# PA3.net
KiCad netlist of a schematic drawn in EAGLE
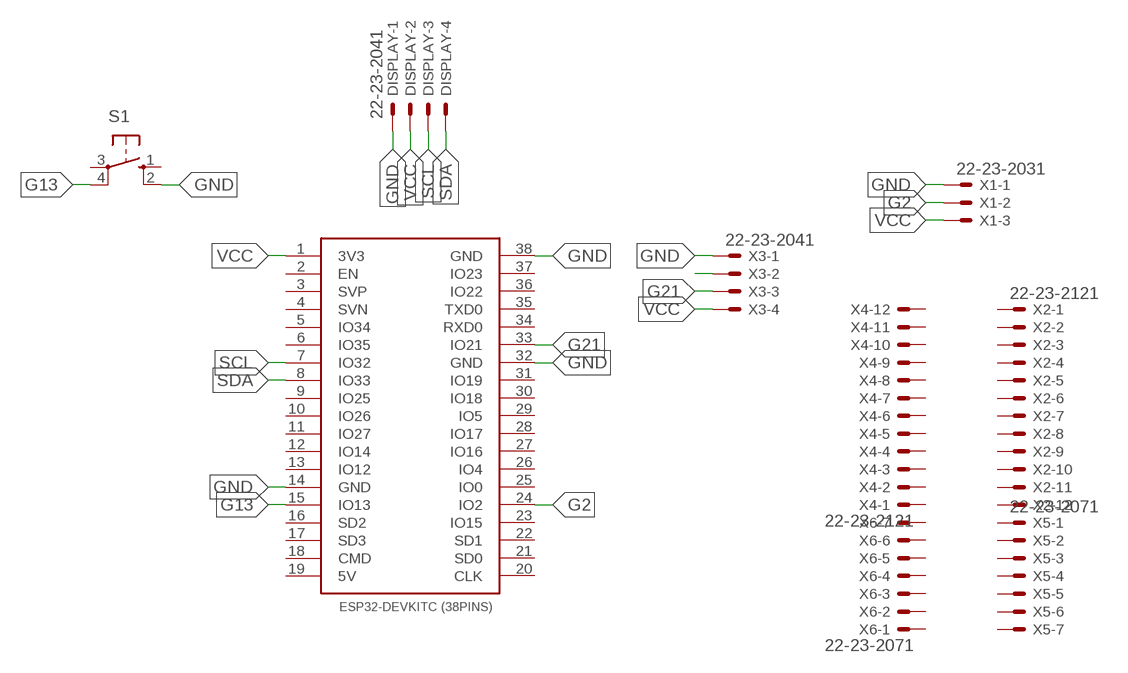
[diagram p0: schematic, sheet 1]

(export (version "E")
  (design (tool "Eeschema 10.0.6"))
  (components
    (comp (ref "DISPLAY")
      (value "22-23-2041")
      (footprint "eagle-import:22-23-2041")
      (fields (field (name "MF") "MOLEX"))
      (libsource (lib "eagle-import") (part "22-23-2041"))
    )
    (comp (ref "ESP32-DEVKITC(38PINS)1")
      (value "ESP32DEVKITC_38PINS")
      (footprint "eagle-import:ESP32-DEVKITC")
      (libsource (lib "eagle-import") (part "ESP32DEVKITC_38PINS"))
    )
    (comp (ref "S1")
      (value "10-XX")
      (footprint "eagle-import:B3F-10XX")
      (fields (field (name "MPN") "B3F-1000"))
      (libsource (lib "eagle-import") (part "10-XX"))
    )
    (comp (ref "X1")
      (value "22-23-2031")
      (footprint "eagle-import:22-23-2031")
      (fields (field (name "MF") "MOLEX"))
      (libsource (lib "eagle-import") (part "22-23-2031"))
    )
    (comp (ref "X2")
      (value "22-23-2121")
      (footprint "eagle-import:22-23-2121")
      (fields (field (name "MF") "MOLEX"))
      (libsource (lib "eagle-import") (part "22-23-2121"))
    )
    (comp (ref "X3")
      (value "22-23-2041")
      (footprint "eagle-import:22-23-2041")
      (fields (field (name "MF") "MOLEX"))
      (libsource (lib "eagle-import") (part "22-23-2041"))
    )
    (comp (ref "X4")
      (value "22-23-2121")
      (footprint "eagle-import:22-23-2121")
      (fields (field (name "MF") "MOLEX"))
      (libsource (lib "eagle-import") (part "22-23-2121"))
    )
    (comp (ref "X5")
      (value "22-23-2071")
      (footprint "eagle-import:22-23-2071")
      (fields (field (name "MF") "MOLEX"))
      (libsource (lib "eagle-import") (part "22-23-2071"))
    )
    (comp (ref "X6")
      (value "22-23-2071")
      (footprint "eagle-import:22-23-2071")
      (fields (field (name "MF") "MOLEX"))
      (libsource (lib "eagle-import") (part "22-23-2071"))
    )
  )
  (nets
    (net (code "1") (name "G2") (class "Default")
      (node (ref "ESP32-DEVKITC(38PINS)1") (pin "24") (pinfunction "IO2_24") (pintype "bidirectional"))
      (node (ref "X1") (pin "2") (pinfunction "S_2") (pintype "passive"))
    )
    (net (code "2") (name "G13") (class "Default")
      (node (ref "ESP32-DEVKITC(38PINS)1") (pin "15") (pinfunction "IO13_15") (pintype "bidirectional"))
      (node (ref "S1") (pin "4") (pinfunction "P1_4") (pintype "passive"))
    )
    (net (code "3") (name "G21") (class "Default")
      (node (ref "ESP32-DEVKITC(38PINS)1") (pin "33") (pinfunction "IO21_33") (pintype "bidirectional"))
      (node (ref "X3") (pin "3") (pinfunction "S_3") (pintype "passive"))
    )
    (net (code "4") (name "GND") (class "Default")
      (node (ref "DISPLAY") (pin "1") (pinfunction "S_1") (pintype "passive"))
      (node (ref "ESP32-DEVKITC(38PINS)1") (pin "14") (pinfunction "GND_14") (pintype "bidirectional"))
      (node (ref "ESP32-DEVKITC(38PINS)1") (pin "32") (pinfunction "GND_32") (pintype "bidirectional"))
      (node (ref "ESP32-DEVKITC(38PINS)1") (pin "38") (pinfunction "GND_38") (pintype "bidirectional"))
      (node (ref "S1") (pin "2") (pinfunction "S1_2") (pintype "passive"))
      (node (ref "X1") (pin "1") (pinfunction "S_1") (pintype "passive"))
      (node (ref "X3") (pin "1") (pinfunction "S_1") (pintype "passive"))
    )
    (net (code "5") (name "SCL") (class "Default")
      (node (ref "DISPLAY") (pin "3") (pinfunction "S_3") (pintype "passive"))
      (node (ref "ESP32-DEVKITC(38PINS)1") (pin "7") (pinfunction "IO32_7") (pintype "bidirectional"))
    )
    (net (code "6") (name "SDA") (class "Default")
      (node (ref "DISPLAY") (pin "4") (pinfunction "S_4") (pintype "passive"))
      (node (ref "ESP32-DEVKITC(38PINS)1") (pin "8") (pinfunction "IO33_8") (pintype "bidirectional"))
    )
    (net (code "7") (name "VCC") (class "Default")
      (node (ref "DISPLAY") (pin "2") (pinfunction "S_2") (pintype "passive"))
      (node (ref "ESP32-DEVKITC(38PINS)1") (pin "1") (pinfunction "3V3_1") (pintype "bidirectional"))
      (node (ref "X1") (pin "3") (pinfunction "S_3") (pintype "passive"))
      (node (ref "X3") (pin "4") (pinfunction "S_4") (pintype "passive"))
    )
    (net (code "8") (name "unconnected-(ESP32-DEVKITC(38PINS)1-5V-Pad19)") (class "Default")
      (node (ref "ESP32-DEVKITC(38PINS)1") (pin "19") (pinfunction "5V_19") (pintype "bidirectional"))
    )
    (net (code "9") (name "unconnected-(ESP32-DEVKITC(38PINS)1-CLK-Pad20)") (class "Default")
      (node (ref "ESP32-DEVKITC(38PINS)1") (pin "20") (pinfunction "CLK_20") (pintype "bidirectional"))
    )
    (net (code "10") (name "unconnected-(ESP32-DEVKITC(38PINS)1-CMD-Pad18)") (class "Default")
      (node (ref "ESP32-DEVKITC(38PINS)1") (pin "18") (pinfunction "CMD_18") (pintype "bidirectional"))
    )
    (net (code "11") (name "unconnected-(ESP32-DEVKITC(38PINS)1-EN-Pad2)") (class "Default")
      (node (ref "ESP32-DEVKITC(38PINS)1") (pin "2") (pinfunction "EN_2") (pintype "bidirectional"))
    )
    (net (code "12") (name "unconnected-(ESP32-DEVKITC(38PINS)1-IO0-Pad25)") (class "Default")
      (node (ref "ESP32-DEVKITC(38PINS)1") (pin "25") (pinfunction "IO0_25") (pintype "bidirectional"))
    )
    (net (code "13") (name "unconnected-(ESP32-DEVKITC(38PINS)1-IO4-Pad26)") (class "Default")
      (node (ref "ESP32-DEVKITC(38PINS)1") (pin "26") (pinfunction "IO4_26") (pintype "bidirectional"))
    )
    (net (code "14") (name "unconnected-(ESP32-DEVKITC(38PINS)1-IO5-Pad29)") (class "Default")
      (node (ref "ESP32-DEVKITC(38PINS)1") (pin "29") (pinfunction "IO5_29") (pintype "bidirectional"))
    )
    (net (code "15") (name "unconnected-(ESP32-DEVKITC(38PINS)1-IO12-Pad13)") (class "Default")
      (node (ref "ESP32-DEVKITC(38PINS)1") (pin "13") (pinfunction "IO12_13") (pintype "bidirectional"))
    )
    (net (code "16") (name "unconnected-(ESP32-DEVKITC(38PINS)1-IO14-Pad12)") (class "Default")
      (node (ref "ESP32-DEVKITC(38PINS)1") (pin "12") (pinfunction "IO14_12") (pintype "bidirectional"))
    )
    (net (code "17") (name "unconnected-(ESP32-DEVKITC(38PINS)1-IO15-Pad23)") (class "Default")
      (node (ref "ESP32-DEVKITC(38PINS)1") (pin "23") (pinfunction "IO15_23") (pintype "bidirectional"))
    )
    (net (code "18") (name "unconnected-(ESP32-DEVKITC(38PINS)1-IO16-Pad27)") (class "Default")
      (node (ref "ESP32-DEVKITC(38PINS)1") (pin "27") (pinfunction "IO16_27") (pintype "bidirectional"))
    )
    (net (code "19") (name "unconnected-(ESP32-DEVKITC(38PINS)1-IO17-Pad28)") (class "Default")
      (node (ref "ESP32-DEVKITC(38PINS)1") (pin "28") (pinfunction "IO17_28") (pintype "bidirectional"))
    )
    (net (code "20") (name "unconnected-(ESP32-DEVKITC(38PINS)1-IO18-Pad30)") (class "Default")
      (node (ref "ESP32-DEVKITC(38PINS)1") (pin "30") (pinfunction "IO18_30") (pintype "bidirectional"))
    )
    (net (code "21") (name "unconnected-(ESP32-DEVKITC(38PINS)1-IO19-Pad31)") (class "Default")
      (node (ref "ESP32-DEVKITC(38PINS)1") (pin "31") (pinfunction "IO19_31") (pintype "bidirectional"))
    )
    (net (code "22") (name "unconnected-(ESP32-DEVKITC(38PINS)1-IO22-Pad36)") (class "Default")
      (node (ref "ESP32-DEVKITC(38PINS)1") (pin "36") (pinfunction "IO22_36") (pintype "bidirectional"))
    )
    (net (code "23") (name "unconnected-(ESP32-DEVKITC(38PINS)1-IO23-Pad37)") (class "Default")
      (node (ref "ESP32-DEVKITC(38PINS)1") (pin "37") (pinfunction "IO23_37") (pintype "bidirectional"))
    )
    (net (code "24") (name "unconnected-(ESP32-DEVKITC(38PINS)1-IO25-Pad9)") (class "Default")
      (node (ref "ESP32-DEVKITC(38PINS)1") (pin "9") (pinfunction "IO25_9") (pintype "bidirectional"))
    )
    (net (code "25") (name "unconnected-(ESP32-DEVKITC(38PINS)1-IO26-Pad10)") (class "Default")
      (node (ref "ESP32-DEVKITC(38PINS)1") (pin "10") (pinfunction "IO26_10") (pintype "bidirectional"))
    )
    (net (code "26") (name "unconnected-(ESP32-DEVKITC(38PINS)1-IO27-Pad11)") (class "Default")
      (node (ref "ESP32-DEVKITC(38PINS)1") (pin "11") (pinfunction "IO27_11") (pintype "bidirectional"))
    )
    (net (code "27") (name "unconnected-(ESP32-DEVKITC(38PINS)1-IO34-Pad5)") (class "Default")
      (node (ref "ESP32-DEVKITC(38PINS)1") (pin "5") (pinfunction "IO34_5") (pintype "bidirectional"))
    )
    (net (code "28") (name "unconnected-(ESP32-DEVKITC(38PINS)1-IO35-Pad6)") (class "Default")
      (node (ref "ESP32-DEVKITC(38PINS)1") (pin "6") (pinfunction "IO35_6") (pintype "bidirectional"))
    )
    (net (code "29") (name "unconnected-(ESP32-DEVKITC(38PINS)1-RXD0-Pad34)") (class "Default")
      (node (ref "ESP32-DEVKITC(38PINS)1") (pin "34") (pinfunction "RXD0_34") (pintype "bidirectional"))
    )
    (net (code "30") (name "unconnected-(ESP32-DEVKITC(38PINS)1-SD0-Pad21)") (class "Default")
      (node (ref "ESP32-DEVKITC(38PINS)1") (pin "21") (pinfunction "SD0_21") (pintype "bidirectional"))
    )
    (net (code "31") (name "unconnected-(ESP32-DEVKITC(38PINS)1-SD1-Pad22)") (class "Default")
      (node (ref "ESP32-DEVKITC(38PINS)1") (pin "22") (pinfunction "SD1_22") (pintype "bidirectional"))
    )
    (net (code "32") (name "unconnected-(ESP32-DEVKITC(38PINS)1-SD2-Pad16)") (class "Default")
      (node (ref "ESP32-DEVKITC(38PINS)1") (pin "16") (pinfunction "SD2_16") (pintype "bidirectional"))
    )
    (net (code "33") (name "unconnected-(ESP32-DEVKITC(38PINS)1-SD3-Pad17)") (class "Default")
      (node (ref "ESP32-DEVKITC(38PINS)1") (pin "17") (pinfunction "SD3_17") (pintype "bidirectional"))
    )
    (net (code "34") (name "unconnected-(ESP32-DEVKITC(38PINS)1-SVN-Pad4)") (class "Default")
      (node (ref "ESP32-DEVKITC(38PINS)1") (pin "4") (pinfunction "SVN_4") (pintype "bidirectional"))
    )
    (net (code "35") (name "unconnected-(ESP32-DEVKITC(38PINS)1-SVP-Pad3)") (class "Default")
      (node (ref "ESP32-DEVKITC(38PINS)1") (pin "3") (pinfunction "SVP_3") (pintype "bidirectional"))
    )
    (net (code "36") (name "unconnected-(ESP32-DEVKITC(38PINS)1-TXD0-Pad35)") (class "Default")
      (node (ref "ESP32-DEVKITC(38PINS)1") (pin "35") (pinfunction "TXD0_35") (pintype "bidirectional"))
    )
    (net (code "37") (name "unconnected-(S1-P-Pad3)") (class "Default")
      (node (ref "S1") (pin "3") (pinfunction "P_3") (pintype "passive"))
    )
    (net (code "38") (name "unconnected-(S1-S-Pad1)") (class "Default")
      (node (ref "S1") (pin "1") (pinfunction "S_1") (pintype "passive"))
    )
    (net (code "39") (name "unconnected-(X2A-S-Pad1)") (class "Default")
      (node (ref "X2") (pin "1") (pinfunction "S_1") (pintype "passive"))
    )
    (net (code "40") (name "unconnected-(X2B-S-Pad10)") (class "Default")
      (node (ref "X2") (pin "10") (pinfunction "S_10") (pintype "passive"))
    )
    (net (code "41") (name "unconnected-(X2C-S-Pad11)") (class "Default")
      (node (ref "X2") (pin "11") (pinfunction "S_11") (pintype "passive"))
    )
    (net (code "42") (name "unconnected-(X2D-S-Pad12)") (class "Default")
      (node (ref "X2") (pin "12") (pinfunction "S_12") (pintype "passive"))
    )
    (net (code "43") (name "unconnected-(X2E-S-Pad2)") (class "Default")
      (node (ref "X2") (pin "2") (pinfunction "S_2") (pintype "passive"))
    )
    (net (code "44") (name "unconnected-(X2F-S-Pad3)") (class "Default")
      (node (ref "X2") (pin "3") (pinfunction "S_3") (pintype "passive"))
    )
    (net (code "45") (name "unconnected-(X2G-S-Pad4)") (class "Default")
      (node (ref "X2") (pin "4") (pinfunction "S_4") (pintype "passive"))
    )
    (net (code "46") (name "unconnected-(X2H-S-Pad5)") (class "Default")
      (node (ref "X2") (pin "5") (pinfunction "S_5") (pintype "passive"))
    )
    (net (code "47") (name "unconnected-(X2I-S-Pad6)") (class "Default")
      (node (ref "X2") (pin "6") (pinfunction "S_6") (pintype "passive"))
    )
    (net (code "48") (name "unconnected-(X2J-S-Pad7)") (class "Default")
      (node (ref "X2") (pin "7") (pinfunction "S_7") (pintype "passive"))
    )
    (net (code "49") (name "unconnected-(X2K-S-Pad8)") (class "Default")
      (node (ref "X2") (pin "8") (pinfunction "S_8") (pintype "passive"))
    )
    (net (code "50") (name "unconnected-(X2L-S-Pad9)") (class "Default")
      (node (ref "X2") (pin "9") (pinfunction "S_9") (pintype "passive"))
    )
    (net (code "51") (name "unconnected-(X3B-S-Pad2)") (class "Default")
      (node (ref "X3") (pin "2") (pinfunction "S_2") (pintype "passive"))
    )
    (net (code "52") (name "unconnected-(X4A-S-Pad1)") (class "Default")
      (node (ref "X4") (pin "1") (pinfunction "S_1") (pintype "passive"))
    )
    (net (code "53") (name "unconnected-(X4B-S-Pad10)") (class "Default")
      (node (ref "X4") (pin "10") (pinfunction "S_10") (pintype "passive"))
    )
    (net (code "54") (name "unconnected-(X4C-S-Pad11)") (class "Default")
      (node (ref "X4") (pin "11") (pinfunction "S_11") (pintype "passive"))
    )
    (net (code "55") (name "unconnected-(X4D-S-Pad12)") (class "Default")
      (node (ref "X4") (pin "12") (pinfunction "S_12") (pintype "passive"))
    )
    (net (code "56") (name "unconnected-(X4E-S-Pad2)") (class "Default")
      (node (ref "X4") (pin "2") (pinfunction "S_2") (pintype "passive"))
    )
    (net (code "57") (name "unconnected-(X4F-S-Pad3)") (class "Default")
      (node (ref "X4") (pin "3") (pinfunction "S_3") (pintype "passive"))
    )
    (net (code "58") (name "unconnected-(X4G-S-Pad4)") (class "Default")
      (node (ref "X4") (pin "4") (pinfunction "S_4") (pintype "passive"))
    )
    (net (code "59") (name "unconnected-(X4H-S-Pad5)") (class "Default")
      (node (ref "X4") (pin "5") (pinfunction "S_5") (pintype "passive"))
    )
    (net (code "60") (name "unconnected-(X4I-S-Pad6)") (class "Default")
      (node (ref "X4") (pin "6") (pinfunction "S_6") (pintype "passive"))
    )
    (net (code "61") (name "unconnected-(X4J-S-Pad7)") (class "Default")
      (node (ref "X4") (pin "7") (pinfunction "S_7") (pintype "passive"))
    )
    (net (code "62") (name "unconnected-(X4K-S-Pad8)") (class "Default")
      (node (ref "X4") (pin "8") (pinfunction "S_8") (pintype "passive"))
    )
    (net (code "63") (name "unconnected-(X4L-S-Pad9)") (class "Default")
      (node (ref "X4") (pin "9") (pinfunction "S_9") (pintype "passive"))
    )
    (net (code "64") (name "unconnected-(X5A-S-Pad1)") (class "Default")
      (node (ref "X5") (pin "1") (pinfunction "S_1") (pintype "passive"))
    )
    (net (code "65") (name "unconnected-(X5B-S-Pad2)") (class "Default")
      (node (ref "X5") (pin "2") (pinfunction "S_2") (pintype "passive"))
    )
    (net (code "66") (name "unconnected-(X5C-S-Pad3)") (class "Default")
      (node (ref "X5") (pin "3") (pinfunction "S_3") (pintype "passive"))
    )
    (net (code "67") (name "unconnected-(X5D-S-Pad4)") (class "Default")
      (node (ref "X5") (pin "4") (pinfunction "S_4") (pintype "passive"))
    )
    (net (code "68") (name "unconnected-(X5E-S-Pad5)") (class "Default")
      (node (ref "X5") (pin "5") (pinfunction "S_5") (pintype "passive"))
    )
    (net (code "69") (name "unconnected-(X5F-S-Pad6)") (class "Default")
      (node (ref "X5") (pin "6") (pinfunction "S_6") (pintype "passive"))
    )
    (net (code "70") (name "unconnected-(X5G-S-Pad7)") (class "Default")
      (node (ref "X5") (pin "7") (pinfunction "S_7") (pintype "passive"))
    )
    (net (code "71") (name "unconnected-(X6A-S-Pad1)") (class "Default")
      (node (ref "X6") (pin "1") (pinfunction "S_1") (pintype "passive"))
    )
    (net (code "72") (name "unconnected-(X6B-S-Pad2)") (class "Default")
      (node (ref "X6") (pin "2") (pinfunction "S_2") (pintype "passive"))
    )
    (net (code "73") (name "unconnected-(X6C-S-Pad3)") (class "Default")
      (node (ref "X6") (pin "3") (pinfunction "S_3") (pintype "passive"))
    )
    (net (code "74") (name "unconnected-(X6D-S-Pad4)") (class "Default")
      (node (ref "X6") (pin "4") (pinfunction "S_4") (pintype "passive"))
    )
    (net (code "75") (name "unconnected-(X6E-S-Pad5)") (class "Default")
      (node (ref "X6") (pin "5") (pinfunction "S_5") (pintype "passive"))
    )
    (net (code "76") (name "unconnected-(X6F-S-Pad6)") (class "Default")
      (node (ref "X6") (pin "6") (pinfunction "S_6") (pintype "passive"))
    )
    (net (code "77") (name "unconnected-(X6G-S-Pad7)") (class "Default")
      (node (ref "X6") (pin "7") (pinfunction "S_7") (pintype "passive"))
    )
  )
)
